# KAMERA_ARAYUZ_STM32L4.net
KiCad netlist of a schematic drawn in EAGLE
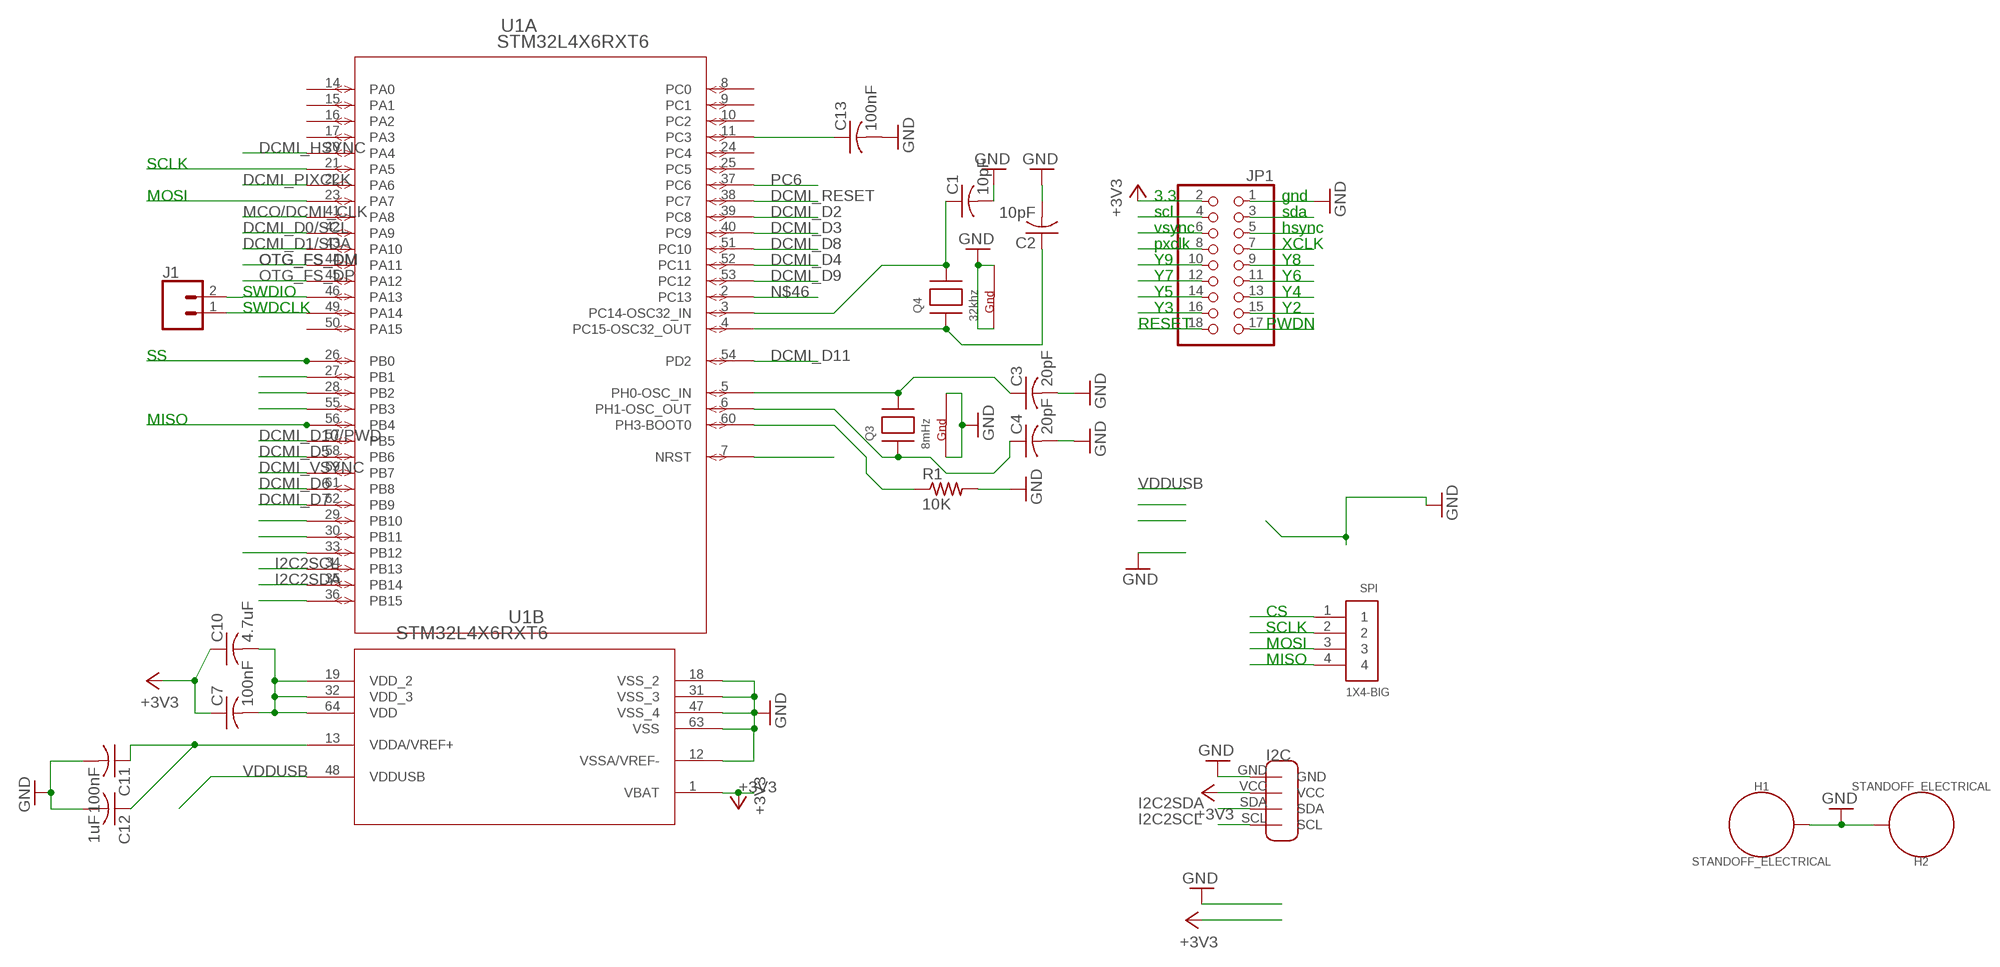
[diagram p0: schematic, sheet 1]

(export (version "E")
  (design (tool "Eeschema 10.0.6"))
  (components
    (comp (ref "C1")
      (value "10pF")
      (footprint "eagle-import:C0805")
      (libsource (lib "eagle-import") (part "C-USC0805"))
    )
    (comp (ref "C2")
      (value "10pF")
      (footprint "eagle-import:C0805")
      (libsource (lib "eagle-import") (part "C-USC0805"))
    )
    (comp (ref "C3")
      (value "20pF")
      (footprint "eagle-import:C0805")
      (libsource (lib "eagle-import") (part "C-USC0805"))
    )
    (comp (ref "C4")
      (value "20pF")
      (footprint "eagle-import:C0805")
      (libsource (lib "eagle-import") (part "C-USC0805"))
    )
    (comp (ref "C7")
      (value "100nF")
      (footprint "eagle-import:C0805")
      (libsource (lib "eagle-import") (part "C-USC0805"))
    )
    (comp (ref "C10")
      (value "4.7uF")
      (footprint "eagle-import:C0805")
      (libsource (lib "eagle-import") (part "C-USC0805"))
    )
    (comp (ref "C11")
      (value "100nF")
      (footprint "eagle-import:C0805")
      (libsource (lib "eagle-import") (part "C-USC0805"))
    )
    (comp (ref "C12")
      (value "1uF")
      (footprint "eagle-import:C0805")
      (libsource (lib "eagle-import") (part "C-USC0805"))
    )
    (comp (ref "C13")
      (value "100nF")
      (footprint "eagle-import:C0805")
      (libsource (lib "eagle-import") (part "C-USC0805"))
    )
    (comp (ref "H1")
      (value "STANDOFF_ELECTRICAL")
      (footprint "eagle-import:STANDOFF-ELECTRICAL")
      (libsource (lib "eagle-import") (part "STANDOFF_ELECTRICAL"))
    )
    (comp (ref "H2")
      (value "STANDOFF_ELECTRICAL")
      (footprint "eagle-import:STANDOFF-ELECTRICAL")
      (libsource (lib "eagle-import") (part "STANDOFF_ELECTRICAL"))
    )
    (comp (ref "J1")
      (value "CONN_02")
      (footprint "eagle-import:1X02")
      (libsource (lib "eagle-import") (part "CONN_02"))
    )
    (comp (ref "JP1")
      (value "PINHD-2X9-CBIG")
      (footprint "eagle-import:2X09-CLEANBIG")
      (libsource (lib "eagle-import") (part "PINHD-2X9-CBIG"))
    )
    (comp (ref "Q3")
      (value "8mHz")
      (footprint "eagle-import:NX3225")
      (libsource (lib "eagle-import") (part "XTAL-4-3225"))
    )
    (comp (ref "Q4")
      (value "32khz")
      (footprint "eagle-import:NX3225")
      (libsource (lib "eagle-import") (part "XTAL-4-3225"))
    )
    (comp (ref "R1")
      (value "10K")
      (footprint "eagle-import:R0805")
      (libsource (lib "eagle-import") (part "R-US_R0805"))
    )
    (comp (ref "SPI")
      (value "1X4-BIG")
      (footprint "eagle-import:1X04-BIG")
      (libsource (lib "eagle-import") (part "1X4-BIG"))
    )
    (comp (ref "U$2")
      (value "I2C")
      (footprint "eagle-import:I2C")
      (libsource (lib "eagle-import") (part "I2C"))
    )
    (comp (ref "U1")
      (value "STM32L4X6RXT6")
      (footprint "eagle-import:LQFP64-10X10MM")
      (fields
        (field (name "MANUFACTURER_PART_NUMBER") "stm32l4x6rxt6")
        (field (name "COPYRIGHT") "Copyright C 2016 Accelerated Designs. All rights reserved")
      )
      (libsource (lib "eagle-import") (part "STM32L4X6RXT6"))
    )
  )
  (nets
    (net (code "1") (name "+3V3") (class "Default")
      (node (ref "C10") (pin "1") (pinfunction "1_1") (pintype "passive"))
      (node (ref "C7") (pin "1") (pinfunction "1_1") (pintype "passive"))
      (node (ref "JP1") (pin "2") (pinfunction "2_2") (pintype "passive"))
      (node (ref "U$2") (pin "VCC") (pinfunction "VCC_VCC") (pintype "bidirectional"))
      (node (ref "U1") (pin "1") (pinfunction "VBAT_1") (pintype "power_in"))
    )
    (net (code "2") (name "/CS") (class "Default")
      (node (ref "SPI") (pin "1") (pinfunction "1_1") (pintype "bidirectional"))
      (node (ref "U1") (pin "26") (pinfunction "PB0_26") (pintype "bidirectional"))
    )
    (net (code "3") (name "/DCMI_D0{slash}SCL") (class "Default")
      (node (ref "JP1") (pin "4") (pinfunction "4_4") (pintype "passive"))
      (node (ref "U1") (pin "42") (pinfunction "PA9_42") (pintype "bidirectional"))
    )
    (net (code "4") (name "/DCMI_D1{slash}SDA") (class "Default")
      (node (ref "JP1") (pin "3") (pinfunction "3_3") (pintype "passive"))
      (node (ref "U1") (pin "43") (pinfunction "PA10_43") (pintype "bidirectional"))
    )
    (net (code "5") (name "/DCMI_D2") (class "Default")
      (node (ref "JP1") (pin "15") (pinfunction "15_15") (pintype "passive"))
      (node (ref "U1") (pin "39") (pinfunction "PC8_39") (pintype "bidirectional"))
    )
    (net (code "6") (name "/DCMI_D3") (class "Default")
      (node (ref "JP1") (pin "16") (pinfunction "16_16") (pintype "passive"))
      (node (ref "U1") (pin "40") (pinfunction "PC9_40") (pintype "bidirectional"))
    )
    (net (code "7") (name "/DCMI_D4") (class "Default")
      (node (ref "JP1") (pin "13") (pinfunction "13_13") (pintype "passive"))
      (node (ref "U1") (pin "52") (pinfunction "PC11_52") (pintype "bidirectional"))
    )
    (net (code "8") (name "/DCMI_D5") (class "Default")
      (node (ref "JP1") (pin "14") (pinfunction "14_14") (pintype "passive"))
      (node (ref "U1") (pin "58") (pinfunction "PB6_58") (pintype "bidirectional"))
    )
    (net (code "9") (name "/DCMI_D6") (class "Default")
      (node (ref "JP1") (pin "11") (pinfunction "11_11") (pintype "passive"))
      (node (ref "U1") (pin "61") (pinfunction "PB8_61") (pintype "bidirectional"))
    )
    (net (code "10") (name "/DCMI_D7") (class "Default")
      (node (ref "JP1") (pin "12") (pinfunction "12_12") (pintype "passive"))
      (node (ref "U1") (pin "62") (pinfunction "PB9_62") (pintype "bidirectional"))
    )
    (net (code "11") (name "/DCMI_D8") (class "Default")
      (node (ref "JP1") (pin "9") (pinfunction "9_9") (pintype "passive"))
      (node (ref "U1") (pin "51") (pinfunction "PC10_51") (pintype "bidirectional"))
    )
    (net (code "12") (name "/DCMI_D9") (class "Default")
      (node (ref "JP1") (pin "10") (pinfunction "10_10") (pintype "passive"))
      (node (ref "U1") (pin "53") (pinfunction "PC12_53") (pintype "bidirectional"))
    )
    (net (code "13") (name "/DCMI_D10{slash}PWD") (class "Default")
      (node (ref "JP1") (pin "17") (pinfunction "17_17") (pintype "passive"))
      (node (ref "U1") (pin "57") (pinfunction "PB5_57") (pintype "bidirectional"))
    )
    (net (code "14") (name "/DCMI_D11") (class "Default")
      (node (ref "U1") (pin "54") (pinfunction "PD2_54") (pintype "bidirectional"))
    )
    (net (code "15") (name "/DCMI_HSYNC") (class "Default")
      (node (ref "JP1") (pin "5") (pinfunction "5_5") (pintype "passive"))
      (node (ref "U1") (pin "20") (pinfunction "PA4_20") (pintype "bidirectional"))
    )
    (net (code "16") (name "/DCMI_PIXCLK") (class "Default")
      (node (ref "JP1") (pin "8") (pinfunction "8_8") (pintype "passive"))
      (node (ref "U1") (pin "22") (pinfunction "PA6_22") (pintype "bidirectional"))
    )
    (net (code "17") (name "/DCMI_RESET") (class "Default")
      (node (ref "JP1") (pin "18") (pinfunction "18_18") (pintype "passive"))
      (node (ref "U1") (pin "38") (pinfunction "PC7_38") (pintype "bidirectional"))
    )
    (net (code "18") (name "/DCMI_VSYNC") (class "Default")
      (node (ref "JP1") (pin "6") (pinfunction "6_6") (pintype "passive"))
      (node (ref "U1") (pin "59") (pinfunction "PB7_59") (pintype "bidirectional"))
    )
    (net (code "19") (name "/I2C2SCL") (class "Default")
      (node (ref "U$2") (pin "SCL") (pinfunction "SCL_SCL") (pintype "bidirectional"))
      (node (ref "U1") (pin "34") (pinfunction "PB13_34") (pintype "bidirectional"))
    )
    (net (code "20") (name "/I2C2SDA") (class "Default")
      (node (ref "U$2") (pin "SDA") (pinfunction "SDA_SDA") (pintype "bidirectional"))
      (node (ref "U1") (pin "35") (pinfunction "PB14_35") (pintype "bidirectional"))
    )
    (net (code "21") (name "/MCO{slash}DCMI_CLK") (class "Default")
      (node (ref "JP1") (pin "7") (pinfunction "7_7") (pintype "passive"))
      (node (ref "U1") (pin "41") (pinfunction "PA8_41") (pintype "bidirectional"))
    )
    (net (code "22") (name "/MISO") (class "Default")
      (node (ref "SPI") (pin "4") (pinfunction "4_4") (pintype "bidirectional"))
      (node (ref "U1") (pin "56") (pinfunction "PB4_56") (pintype "bidirectional"))
    )
    (net (code "23") (name "/MOSI") (class "Default")
      (node (ref "SPI") (pin "3") (pinfunction "3_3") (pintype "bidirectional"))
      (node (ref "U1") (pin "23") (pinfunction "PA7_23") (pintype "bidirectional"))
    )
    (net (code "24") (name "/N$46") (class "Default")
      (node (ref "U1") (pin "2") (pinfunction "PC13_2") (pintype "bidirectional"))
    )
    (net (code "25") (name "/OTG_FS_DM") (class "Default")
      (node (ref "U1") (pin "44") (pinfunction "PA11_44") (pintype "bidirectional"))
    )
    (net (code "26") (name "/OTG_FS_DP") (class "Default")
      (node (ref "U1") (pin "45") (pinfunction "PA12_45") (pintype "bidirectional"))
    )
    (net (code "27") (name "/PC6") (class "Default")
      (node (ref "U1") (pin "37") (pinfunction "PC6_37") (pintype "bidirectional"))
    )
    (net (code "28") (name "/SCLK") (class "Default")
      (node (ref "SPI") (pin "2") (pinfunction "2_2") (pintype "bidirectional"))
      (node (ref "U1") (pin "21") (pinfunction "PA5_21") (pintype "bidirectional"))
    )
    (net (code "29") (name "/VDDUSB") (class "Default")
      (node (ref "U1") (pin "48") (pinfunction "VDDUSB_48") (pintype "power_in"))
    )
    (net (code "30") (name "GND") (class "Default")
      (node (ref "C1") (pin "2") (pinfunction "2_2") (pintype "passive"))
      (node (ref "C11") (pin "2") (pinfunction "2_2") (pintype "passive"))
      (node (ref "C12") (pin "2") (pinfunction "2_2") (pintype "passive"))
      (node (ref "C13") (pin "2") (pinfunction "2_2") (pintype "passive"))
      (node (ref "C2") (pin "2") (pinfunction "2_2") (pintype "passive"))
      (node (ref "C3") (pin "2") (pinfunction "2_2") (pintype "passive"))
      (node (ref "C4") (pin "2") (pinfunction "2_2") (pintype "passive"))
      (node (ref "H1") (pin "P1") (pinfunction "P$1_P1") (pintype "bidirectional"))
      (node (ref "H2") (pin "P1") (pinfunction "P$1_P1") (pintype "bidirectional"))
      (node (ref "JP1") (pin "1") (pinfunction "1_1") (pintype "passive"))
      (node (ref "Q3") (pin "2") (pinfunction "G2_2") (pintype "power_in"))
      (node (ref "Q3") (pin "4") (pinfunction "G1_4") (pintype "power_in"))
      (node (ref "Q4") (pin "2") (pinfunction "G2_2") (pintype "power_in"))
      (node (ref "Q4") (pin "4") (pinfunction "G1_4") (pintype "power_in"))
      (node (ref "R1") (pin "2") (pinfunction "2_2") (pintype "passive"))
      (node (ref "U$2") (pin "GND") (pinfunction "GND_GND") (pintype "bidirectional"))
      (node (ref "U1") (pin "12") (pinfunction "VSSA/VREF-_12") (pintype "power_in"))
      (node (ref "U1") (pin "18") (pinfunction "VSS_2_18") (pintype "power_in"))
      (node (ref "U1") (pin "31") (pinfunction "VSS_3_31") (pintype "power_in"))
      (node (ref "U1") (pin "47") (pinfunction "VSS_4_47") (pintype "power_in"))
      (node (ref "U1") (pin "63") (pinfunction "VSS_63") (pintype "power_in"))
    )
    (net (code "31") (name "Net-(Q3-X1)") (class "Default")
      (node (ref "C4") (pin "1") (pinfunction "1_1") (pintype "passive"))
      (node (ref "Q3") (pin "1") (pinfunction "X1_1") (pintype "bidirectional"))
      (node (ref "U1") (pin "6") (pinfunction "PH1-OSC_OUT_6") (pintype "bidirectional"))
    )
    (net (code "32") (name "Net-(Q3-X2)") (class "Default")
      (node (ref "C3") (pin "1") (pinfunction "1_1") (pintype "passive"))
      (node (ref "Q3") (pin "3") (pinfunction "X2_3") (pintype "bidirectional"))
      (node (ref "U1") (pin "5") (pinfunction "PH0-OSC_IN_5") (pintype "bidirectional"))
    )
    (net (code "33") (name "Net-(Q4-X1)") (class "Default")
      (node (ref "C2") (pin "1") (pinfunction "1_1") (pintype "passive"))
      (node (ref "Q4") (pin "1") (pinfunction "X1_1") (pintype "bidirectional"))
      (node (ref "U1") (pin "4") (pinfunction "PC15-OSC32_OUT_4") (pintype "bidirectional"))
    )
    (net (code "34") (name "Net-(Q4-X2)") (class "Default")
      (node (ref "C1") (pin "1") (pinfunction "1_1") (pintype "passive"))
      (node (ref "Q4") (pin "3") (pinfunction "X2_3") (pintype "bidirectional"))
      (node (ref "U1") (pin "3") (pinfunction "PC14-OSC32_IN_3") (pintype "bidirectional"))
    )
    (net (code "35") (name "Net-(U1A-PA13)") (class "Default")
      (node (ref "J1") (pin "2") (pinfunction "2_2") (pintype "passive"))
      (node (ref "U1") (pin "46") (pinfunction "PA13_46") (pintype "bidirectional"))
    )
    (net (code "36") (name "Net-(U1A-PA14)") (class "Default")
      (node (ref "J1") (pin "1") (pinfunction "1_1") (pintype "passive"))
      (node (ref "U1") (pin "49") (pinfunction "PA14_49") (pintype "bidirectional"))
    )
    (net (code "37") (name "Net-(U1A-PC3)") (class "Default")
      (node (ref "C13") (pin "1") (pinfunction "1_1") (pintype "passive"))
      (node (ref "U1") (pin "11") (pinfunction "PC3_11") (pintype "bidirectional"))
    )
    (net (code "38") (name "Net-(U1A-PH3-BOOT0)") (class "Default")
      (node (ref "R1") (pin "1") (pinfunction "1_1") (pintype "passive"))
      (node (ref "U1") (pin "60") (pinfunction "PH3-BOOT0_60") (pintype "bidirectional"))
    )
    (net (code "39") (name "Net-(U1B-VDD)") (class "Default")
      (node (ref "C10") (pin "2") (pinfunction "2_2") (pintype "passive"))
      (node (ref "C7") (pin "2") (pinfunction "2_2") (pintype "passive"))
      (node (ref "U1") (pin "19") (pinfunction "VDD_2_19") (pintype "power_in"))
      (node (ref "U1") (pin "32") (pinfunction "VDD_3_32") (pintype "power_in"))
      (node (ref "U1") (pin "64") (pinfunction "VDD_64") (pintype "power_in"))
    )
    (net (code "40") (name "Net-(U1B-VDDA{slash}VREF+)") (class "Default")
      (node (ref "C11") (pin "1") (pinfunction "1_1") (pintype "passive"))
      (node (ref "C12") (pin "1") (pinfunction "1_1") (pintype "passive"))
      (node (ref "U1") (pin "13") (pinfunction "VDDA/VREF+_13") (pintype "power_in"))
    )
    (net (code "41") (name "unconnected-(U1A-NRST-Pad7)") (class "Default")
      (node (ref "U1") (pin "7") (pinfunction "NRST_7") (pintype "bidirectional"))
    )
    (net (code "42") (name "unconnected-(U1A-PA0-Pad14)") (class "Default")
      (node (ref "U1") (pin "14") (pinfunction "PA0_14") (pintype "bidirectional"))
    )
    (net (code "43") (name "unconnected-(U1A-PA1-Pad15)") (class "Default")
      (node (ref "U1") (pin "15") (pinfunction "PA1_15") (pintype "bidirectional"))
    )
    (net (code "44") (name "unconnected-(U1A-PA2-Pad16)") (class "Default")
      (node (ref "U1") (pin "16") (pinfunction "PA2_16") (pintype "bidirectional"))
    )
    (net (code "45") (name "unconnected-(U1A-PA3-Pad17)") (class "Default")
      (node (ref "U1") (pin "17") (pinfunction "PA3_17") (pintype "bidirectional"))
    )
    (net (code "46") (name "unconnected-(U1A-PA15-Pad50)") (class "Default")
      (node (ref "U1") (pin "50") (pinfunction "PA15_50") (pintype "bidirectional"))
    )
    (net (code "47") (name "unconnected-(U1A-PB1-Pad27)") (class "Default")
      (node (ref "U1") (pin "27") (pinfunction "PB1_27") (pintype "bidirectional"))
    )
    (net (code "48") (name "unconnected-(U1A-PB2-Pad28)") (class "Default")
      (node (ref "U1") (pin "28") (pinfunction "PB2_28") (pintype "bidirectional"))
    )
    (net (code "49") (name "unconnected-(U1A-PB3-Pad55)") (class "Default")
      (node (ref "U1") (pin "55") (pinfunction "PB3_55") (pintype "bidirectional"))
    )
    (net (code "50") (name "unconnected-(U1A-PB10-Pad29)") (class "Default")
      (node (ref "U1") (pin "29") (pinfunction "PB10_29") (pintype "bidirectional"))
    )
    (net (code "51") (name "unconnected-(U1A-PB11-Pad30)") (class "Default")
      (node (ref "U1") (pin "30") (pinfunction "PB11_30") (pintype "bidirectional"))
    )
    (net (code "52") (name "unconnected-(U1A-PB12-Pad33)") (class "Default")
      (node (ref "U1") (pin "33") (pinfunction "PB12_33") (pintype "bidirectional"))
    )
    (net (code "53") (name "unconnected-(U1A-PB15-Pad36)") (class "Default")
      (node (ref "U1") (pin "36") (pinfunction "PB15_36") (pintype "bidirectional"))
    )
    (net (code "54") (name "unconnected-(U1A-PC0-Pad8)") (class "Default")
      (node (ref "U1") (pin "8") (pinfunction "PC0_8") (pintype "bidirectional"))
    )
    (net (code "55") (name "unconnected-(U1A-PC1-Pad9)") (class "Default")
      (node (ref "U1") (pin "9") (pinfunction "PC1_9") (pintype "bidirectional"))
    )
    (net (code "56") (name "unconnected-(U1A-PC2-Pad10)") (class "Default")
      (node (ref "U1") (pin "10") (pinfunction "PC2_10") (pintype "bidirectional"))
    )
    (net (code "57") (name "unconnected-(U1A-PC4-Pad24)") (class "Default")
      (node (ref "U1") (pin "24") (pinfunction "PC4_24") (pintype "bidirectional"))
    )
    (net (code "58") (name "unconnected-(U1A-PC5-Pad25)") (class "Default")
      (node (ref "U1") (pin "25") (pinfunction "PC5_25") (pintype "bidirectional"))
    )
  )
)
